# mw_ltb_full_v2_0_0.net
KiCad netlist of a schematic drawn in EAGLE
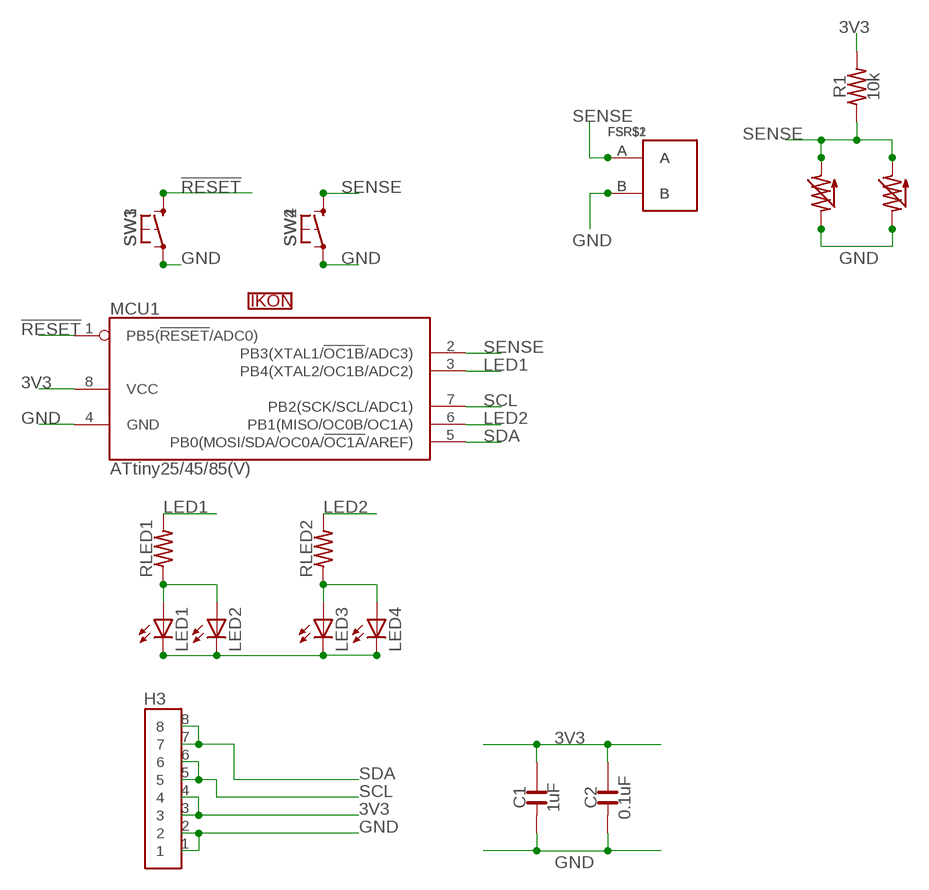
[diagram p0: schematic, sheet 1]

(export (version "E")
  (design (tool "Eeschema 10.0.6"))
  (components
    (comp (ref "C1")
      (value "1uF")
      (footprint "eagle-import:0603_YAGEO")
      (libsource (lib "eagle-import") (part "CAPACITOR-0603"))
    )
    (comp (ref "C2")
      (value "0.1uF")
      (footprint "eagle-import:0603_YAGEO")
      (libsource (lib "eagle-import") (part "CAPACITOR-0603"))
    )
    (comp (ref "FSR$1")
      (value "FSR_PAD88X44_P2B")
      (footprint "eagle-import:FSR_PAD_88X44_P2B")
      (libsource (lib "eagle-import") (part "FSR_PAD88X44_P2B"))
    )
    (comp (ref "FSR$2")
      (value "FSR_PAD88X44_P2B")
      (footprint "eagle-import:FSR_PAD_88X44_P2B")
      (libsource (lib "eagle-import") (part "FSR_PAD88X44_P2B"))
    )
    (comp (ref "H3")
      (value "HEADER_8P-0.1\"_2X4-SMD-SULLINS")
      (footprint "eagle-import:HEADER-0.1__2X4-SMD-SULLINS")
      (libsource (lib "eagle-import") (part "HEADER_8P-0.1{dblquote}_2X4-SMD-SULLINS"))
    )
    (comp (ref "LED1")
      (value "LED-ZBEND_RM")
      (footprint "eagle-import:Z-BEND_RM")
      (libsource (lib "eagle-import") (part "LED-ZBEND_RM"))
    )
    (comp (ref "LED2")
      (value "LED-ZBEND_RM")
      (footprint "eagle-import:Z-BEND_RM")
      (libsource (lib "eagle-import") (part "LED-ZBEND_RM"))
    )
    (comp (ref "LED3")
      (value "LED-ZBEND_RM")
      (footprint "eagle-import:Z-BEND_RM")
      (libsource (lib "eagle-import") (part "LED-ZBEND_RM"))
    )
    (comp (ref "LED4")
      (value "LED-ZBEND_RM")
      (footprint "eagle-import:Z-BEND_RM")
      (libsource (lib "eagle-import") (part "LED-ZBEND_RM"))
    )
    (comp (ref "MCU1")
      (value "ATMEL_ATTINY25/45/85(V)-SOIC_DUAL")
      (footprint "eagle-import:SOIC-8_DUAL")
      (libsource (lib "eagle-import") (part "ATMEL_ATTINY25/45/85(V)-SOIC_DUAL"))
    )
    (comp (ref "R1")
      (value "10k")
      (footprint "eagle-import:0603_YAGEO")
      (libsource (lib "eagle-import") (part "RESISTOR-0603"))
    )
    (comp (ref "RLED1")
      (value "RESISTOR-0603")
      (footprint "eagle-import:0603_YAGEO")
      (libsource (lib "eagle-import") (part "RESISTOR-0603"))
    )
    (comp (ref "RLED2")
      (value "RESISTOR-0603")
      (footprint "eagle-import:0603_YAGEO")
      (libsource (lib "eagle-import") (part "RESISTOR-0603"))
    )
    (comp (ref "SW1")
      (value "SWITCH_SPST-KMT0")
      (footprint "eagle-import:SWITCH_KMT0")
      (libsource (lib "eagle-import") (part "SWITCH_SPST-KMT0"))
    )
    (comp (ref "SW2")
      (value "SWITCH_SPST-KMT0")
      (footprint "eagle-import:SWITCH_KMT0")
      (libsource (lib "eagle-import") (part "SWITCH_SPST-KMT0"))
    )
    (comp (ref "SW3")
      (value "SWITCH_SPST-TL3315")
      (footprint "eagle-import:SWITCH_TL3315")
      (libsource (lib "eagle-import") (part "SWITCH_SPST-TL3315"))
    )
    (comp (ref "SW4")
      (value "SWITCH_SPST-TL3315")
      (footprint "eagle-import:SWITCH_TL3315")
      (libsource (lib "eagle-import") (part "SWITCH_SPST-TL3315"))
    )
    (comp (ref "U$1")
      (value "FSR_PINS")
      (footprint "eagle-import:FSR_0.1_-PITCH_PADS-0.05_X0.5_")
      (libsource (lib "eagle-import") (part "FSR_PINSJUMBO_SMD"))
    )
    (comp (ref "U$2")
      (value "FSR_PLACE")
      (footprint "eagle-import:FSR_1.5[IN]_SQR")
      (libsource (lib "eagle-import") (part "FSR_PLACE1.5{dblquote}SQR"))
    )
    (comp (ref "U$3")
      (value "FSR_PINS")
      (footprint "eagle-import:FSR_0.1_-PITCH_PADS-0.05_X0.5_")
      (libsource (lib "eagle-import") (part "FSR_PINSJUMBO_SMD"))
    )
    (comp (ref "U$4")
      (value "FSR_PLACE")
      (footprint "eagle-import:FSR_1.5[IN]_SQR")
      (libsource (lib "eagle-import") (part "FSR_PLACE1.5{dblquote}SQR"))
    )
    (comp (ref "U$5")
      (value "FSR_PLACE")
      (footprint "eagle-import:FSR_1.5[IN]_SQR")
      (libsource (lib "eagle-import") (part "FSR_PLACE1.5{dblquote}SQR"))
    )
    (comp (ref "U$6")
      (value "FSR_PLACE")
      (footprint "eagle-import:FSR_1.5[IN]_SQR")
      (libsource (lib "eagle-import") (part "FSR_PLACE1.5{dblquote}SQR"))
    )
    (comp (ref "U$9")
      (value "FSR_PINS")
      (footprint "eagle-import:FSR_0.1_-PITCH_PADS-0.05_X0.5_")
      (libsource (lib "eagle-import") (part "FSR_PINSJUMBO_SMD"))
    )
    (comp (ref "U$10")
      (value "FSR_PINS")
      (footprint "eagle-import:FSR_0.1_-PITCH_PADS-0.05_X0.5_")
      (libsource (lib "eagle-import") (part "FSR_PINSJUMBO_SMD"))
    )
    (comp (ref "U$11")
      (value "IKONLEARNING-20MIL")
      (footprint "eagle-import:IKON_LEARNING_20MIL")
      (libsource (lib "eagle-import") (part "IKONLEARNING-20MIL"))
    )
  )
  (nets
    (net (code "1") (name "/3V3") (class "Default")
      (node (ref "C1") (pin "2") (pinfunction "P$2_2") (pintype "passive"))
      (node (ref "C2") (pin "2") (pinfunction "P$2_2") (pintype "passive"))
      (node (ref "H3") (pin "3") (pinfunction "3_3") (pintype "bidirectional"))
      (node (ref "H3") (pin "4") (pinfunction "4_4") (pintype "bidirectional"))
      (node (ref "MCU1") (pin "8") (pinfunction "VCC_8") (pintype "bidirectional"))
      (node (ref "R1") (pin "2") (pinfunction "2_2") (pintype "passive"))
    )
    (net (code "2") (name "/GND") (class "Default")
      (node (ref "C1") (pin "1") (pinfunction "P$1_1") (pintype "passive"))
      (node (ref "C2") (pin "1") (pinfunction "P$1_1") (pintype "passive"))
      (node (ref "FSR$1") (pin "B") (pinfunction "B_B") (pintype "bidirectional"))
      (node (ref "FSR$2") (pin "B") (pinfunction "B_B") (pintype "bidirectional"))
      (node (ref "H3") (pin "1") (pinfunction "1_1") (pintype "bidirectional"))
      (node (ref "H3") (pin "2") (pinfunction "2_2") (pintype "bidirectional"))
      (node (ref "LED1") (pin "K") (pinfunction "C_K") (pintype "passive"))
      (node (ref "LED2") (pin "K") (pinfunction "C_K") (pintype "passive"))
      (node (ref "LED3") (pin "K") (pinfunction "C_K") (pintype "passive"))
      (node (ref "LED4") (pin "K") (pinfunction "C_K") (pintype "passive"))
      (node (ref "MCU1") (pin "4") (pinfunction "GND_4") (pintype "bidirectional"))
      (node (ref "SW1") (pin "2@1") (pinfunction "2_2@1") (pintype "passive"))
      (node (ref "SW1") (pin "2@2") (pinfunction "2_2@2") (pintype "passive"))
      (node (ref "SW2") (pin "2@1") (pinfunction "2_2@1") (pintype "passive"))
      (node (ref "SW2") (pin "2@2") (pinfunction "2_2@2") (pintype "passive"))
      (node (ref "SW3") (pin "2@1") (pinfunction "2_2@1") (pintype "passive"))
      (node (ref "SW3") (pin "2@2") (pinfunction "2_2@2") (pintype "passive"))
      (node (ref "SW4") (pin "2@1") (pinfunction "2_2@1") (pintype "passive"))
      (node (ref "SW4") (pin "2@2") (pinfunction "2_2@2") (pintype "passive"))
      (node (ref "U$1") (pin "P$1") (pinfunction "P$1_P$1") (pintype "bidirectional"))
      (node (ref "U$10") (pin "P$1") (pinfunction "P$1_P$1") (pintype "bidirectional"))
      (node (ref "U$3") (pin "P$2") (pinfunction "P$2_P$2") (pintype "bidirectional"))
      (node (ref "U$9") (pin "P$2") (pinfunction "P$2_P$2") (pintype "bidirectional"))
    )
    (net (code "3") (name "/LED1") (class "Default")
      (node (ref "MCU1") (pin "3") (pinfunction "PB4(XTAL2/OC1B/ADC2)_3") (pintype "bidirectional"))
      (node (ref "RLED1") (pin "2") (pinfunction "2_2") (pintype "passive"))
    )
    (net (code "4") (name "/LED2") (class "Default")
      (node (ref "MCU1") (pin "6") (pinfunction "PB1(MISO/OC0B/OC1A)_6") (pintype "bidirectional"))
      (node (ref "RLED2") (pin "2") (pinfunction "2_2") (pintype "passive"))
    )
    (net (code "5") (name "/SCL") (class "Default")
      (node (ref "H3") (pin "5") (pinfunction "5_5") (pintype "bidirectional"))
      (node (ref "H3") (pin "6") (pinfunction "6_6") (pintype "bidirectional"))
      (node (ref "MCU1") (pin "7") (pinfunction "PB2(SCK/SCL/ADC1)_7") (pintype "bidirectional"))
    )
    (net (code "6") (name "/SDA") (class "Default")
      (node (ref "H3") (pin "7") (pinfunction "7_7") (pintype "bidirectional"))
      (node (ref "H3") (pin "8") (pinfunction "8_8") (pintype "bidirectional"))
      (node (ref "MCU1") (pin "5") (pinfunction "PB0(MOSI/SDA/OC0A/~{OC1A}/AREF)_5") (pintype "bidirectional"))
    )
    (net (code "7") (name "/SENSE") (class "Default")
      (node (ref "FSR$1") (pin "A") (pinfunction "A_A") (pintype "bidirectional"))
      (node (ref "FSR$2") (pin "A") (pinfunction "A_A") (pintype "bidirectional"))
      (node (ref "MCU1") (pin "2") (pinfunction "PB3(XTAL1/~{OC1B}/ADC3)_2") (pintype "bidirectional"))
      (node (ref "R1") (pin "1") (pinfunction "1_1") (pintype "passive"))
      (node (ref "SW2") (pin "1@1") (pinfunction "1_1@1") (pintype "passive"))
      (node (ref "SW2") (pin "1@2") (pinfunction "1_1@2") (pintype "passive"))
      (node (ref "SW4") (pin "1@1") (pinfunction "1_1@1") (pintype "passive"))
      (node (ref "SW4") (pin "1@2") (pinfunction "1_1@2") (pintype "passive"))
      (node (ref "U$1") (pin "P$2") (pinfunction "P$2_P$2") (pintype "bidirectional"))
      (node (ref "U$10") (pin "P$2") (pinfunction "P$2_P$2") (pintype "bidirectional"))
      (node (ref "U$3") (pin "P$1") (pinfunction "P$1_P$1") (pintype "bidirectional"))
      (node (ref "U$9") (pin "P$1") (pinfunction "P$1_P$1") (pintype "bidirectional"))
    )
    (net (code "8") (name "/~{RESET}") (class "Default")
      (node (ref "MCU1") (pin "1") (pinfunction "PB5(~{RESET}/ADC0)_1") (pintype "bidirectional"))
      (node (ref "SW1") (pin "1@1") (pinfunction "1_1@1") (pintype "passive"))
      (node (ref "SW1") (pin "1@2") (pinfunction "1_1@2") (pintype "passive"))
      (node (ref "SW3") (pin "1@1") (pinfunction "1_1@1") (pintype "passive"))
      (node (ref "SW3") (pin "1@2") (pinfunction "1_1@2") (pintype "passive"))
    )
    (net (code "9") (name "Net-(LED1-PadA)") (class "Default")
      (node (ref "LED1") (pin "A") (pinfunction "A_A") (pintype "passive"))
      (node (ref "LED2") (pin "A") (pinfunction "A_A") (pintype "passive"))
      (node (ref "RLED1") (pin "1") (pinfunction "1_1") (pintype "passive"))
    )
    (net (code "10") (name "Net-(LED3-PadA)") (class "Default")
      (node (ref "LED3") (pin "A") (pinfunction "A_A") (pintype "passive"))
      (node (ref "LED4") (pin "A") (pinfunction "A_A") (pintype "passive"))
      (node (ref "RLED2") (pin "1") (pinfunction "1_1") (pintype "passive"))
    )
  )
)
